# PCBA-2121-01.net
KiCad netlist of a schematic drawn in Altium Designer
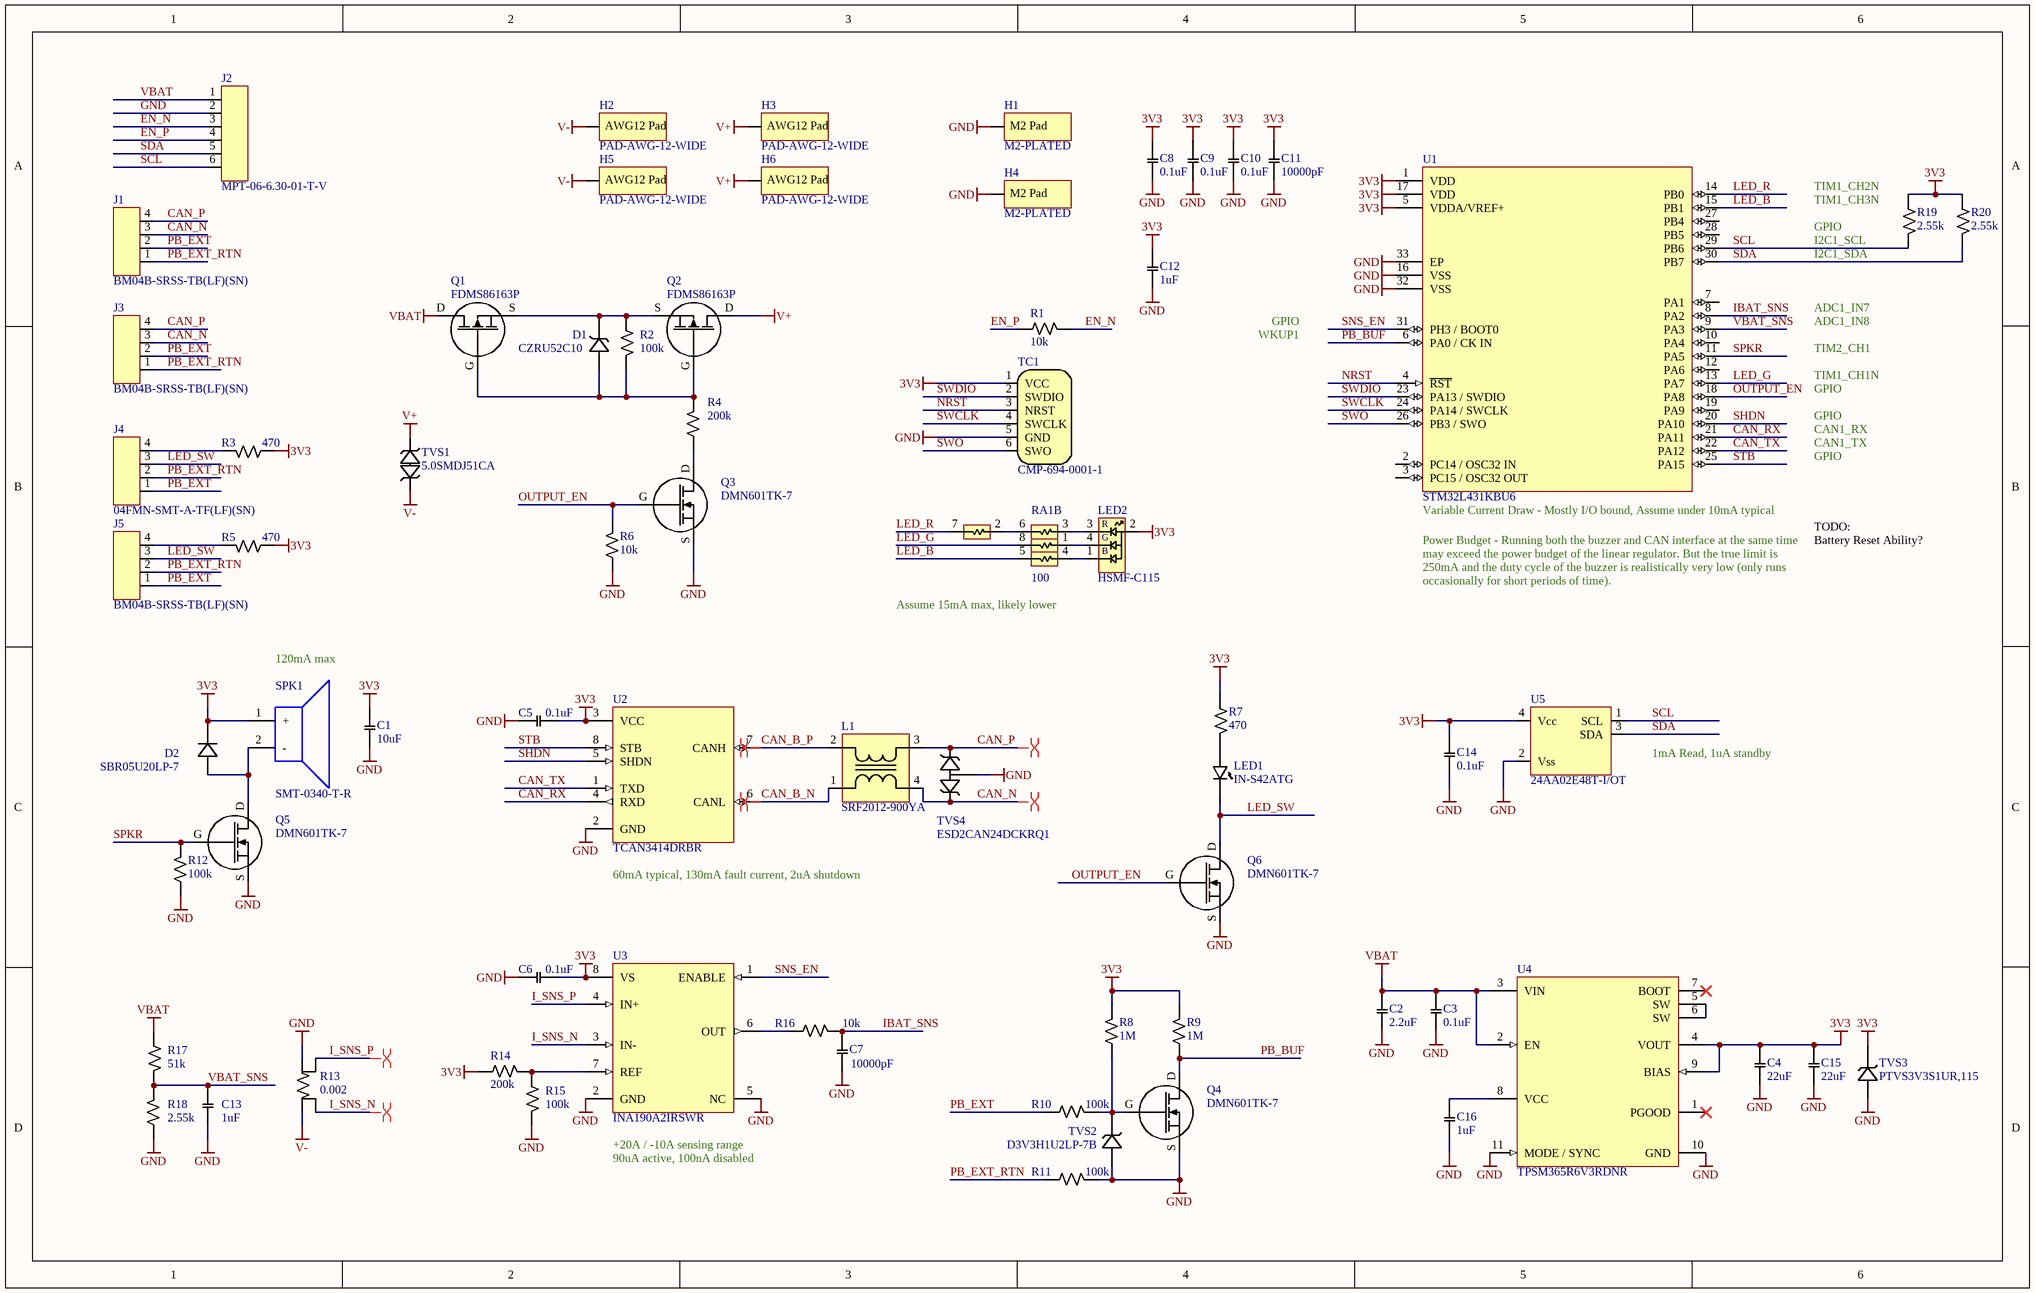
[diagram p0: PCBA-2121-01.SchDoc]

(export (version "E")
  (design (tool "Eeschema 10.0.6"))
  (components
    (comp (ref "C1")
      (value "C-10uf-X5R-16V-10%-0603")
      (footprint "C0603")
      (description "Capacitor Ceramic 10uF 16V X5R 10% SMD 0603")
      (fields (field (name "CAPACITANCE") "10uF") (field (name "TOLERANCE") "10%"))
      (libsource (lib "Hebi Robotics") (part "Capacitor"))
    )
    (comp (ref "C2")
      (value "C-2.2uf-X7R-100V-10%-1206")
      (footprint "C1206")
      (description "Capacitor Ceramic 2.2uF 100V X7R 10% SMD 1206")
      (fields (field (name "CAPACITANCE") "2.2uF") (field (name "TOLERANCE") "±10%"))
      (libsource (lib "Hebi Robotics") (part "Capacitor"))
    )
    (comp (ref "C3")
      (value "C-0.1uf-X7R-100V-20%-0603")
      (footprint "C0603")
      (description "Capacitor Ceramic 0.1uF 100V X7R 20% SMD 0603")
      (fields (field (name "CAPACITANCE") "0.1uF") (field (name "TOLERANCE") "±20%"))
      (libsource (lib "Hebi Robotics") (part "Capacitor"))
    )
    (comp (ref "C4")
      (value "C-22uf-X5R-25V-20%-1206")
      (footprint "C1206")
      (description "Capacitor Ceramic 22uF 25V X5R 20% SMD 1206")
      (fields (field (name "CAPACITANCE") "22uF") (field (name "TOLERANCE") "20%"))
      (libsource (lib "Hebi Robotics") (part "Capacitor"))
    )
    (comp (ref "C5")
      (value "C-0.1uf-X7R-25V-10%-0402")
      (footprint "C0402")
      (description "Capacitor Ceramic 0.1uF 25V X7R 10% SMD 0402")
      (fields (field (name "CAPACITANCE") "0.1uF") (field (name "TOLERANCE") "10%"))
      (libsource (lib "Hebi Robotics") (part "Capacitor"))
    )
    (comp (ref "C6")
      (value "C-0.1uf-X7R-25V-10%-0402")
      (footprint "C0402")
      (description "Capacitor Ceramic 0.1uF 25V X7R 10% SMD 0402")
      (fields (field (name "CAPACITANCE") "0.1uF") (field (name "TOLERANCE") "10%"))
      (libsource (lib "Hebi Robotics") (part "Capacitor"))
    )
    (comp (ref "C7")
      (value "C-10000pf-X7R-50V-10%-0402")
      (footprint "C0402")
      (description "Capacitor Ceramic 10000pF 50V X7R 10% SMD 0402")
      (fields (field (name "TOLERANCE") "10%") (field (name "CAPACITANCE") "10000pF"))
      (libsource (lib "Hebi Robotics") (part "Capacitor"))
    )
    (comp (ref "C8")
      (value "C-0.1uf-X7R-25V-10%-0402")
      (footprint "C0402")
      (description "Capacitor Ceramic 0.1uF 25V X7R 10% SMD 0402")
      (fields (field (name "CAPACITANCE") "0.1uF") (field (name "TOLERANCE") "10%"))
      (libsource (lib "Hebi Robotics") (part "Capacitor"))
    )
    (comp (ref "C9")
      (value "C-0.1uf-X7R-25V-10%-0402")
      (footprint "C0402")
      (description "Capacitor Ceramic 0.1uF 25V X7R 10% SMD 0402")
      (fields (field (name "CAPACITANCE") "0.1uF") (field (name "TOLERANCE") "10%"))
      (libsource (lib "Hebi Robotics") (part "Capacitor"))
    )
    (comp (ref "C10")
      (value "C-0.1uf-X7R-25V-10%-0402")
      (footprint "C0402")
      (description "Capacitor Ceramic 0.1uF 25V X7R 10% SMD 0402")
      (fields (field (name "CAPACITANCE") "0.1uF") (field (name "TOLERANCE") "10%"))
      (libsource (lib "Hebi Robotics") (part "Capacitor"))
    )
    (comp (ref "C11")
      (value "C-10000pf-X7R-50V-10%-0402")
      (footprint "C0402")
      (description "Capacitor Ceramic 10000pF 50V X7R 10% SMD 0402")
      (fields (field (name "TOLERANCE") "10%") (field (name "CAPACITANCE") "10000pF"))
      (libsource (lib "Hebi Robotics") (part "Capacitor"))
    )
    (comp (ref "C12")
      (value "C-1uf-X5R-25V-10%-0402")
      (footprint "C0402")
      (description "Capacitor Ceramic 1uF 25V X5R 10% SMD 0402")
      (fields (field (name "CAPACITANCE") "1uF") (field (name "TOLERANCE") "±10%"))
      (libsource (lib "Hebi Robotics") (part "Capacitor"))
    )
    (comp (ref "C13")
      (value "C-1uf-X5R-25V-10%-0402")
      (footprint "C0402")
      (description "Capacitor Ceramic 1uF 25V X5R 10% SMD 0402")
      (fields (field (name "CAPACITANCE") "1uF") (field (name "TOLERANCE") "±10%"))
      (libsource (lib "Hebi Robotics") (part "Capacitor"))
    )
    (comp (ref "C14")
      (value "C-0.1uf-X7R-25V-10%-0402")
      (footprint "C0402")
      (description "Capacitor Ceramic 0.1uF 25V X7R 10% SMD 0402")
      (fields (field (name "CAPACITANCE") "0.1uF") (field (name "TOLERANCE") "10%"))
      (libsource (lib "Hebi Robotics") (part "Capacitor"))
    )
    (comp (ref "C15")
      (value "C-22uf-X5R-25V-20%-1206")
      (footprint "C1206")
      (description "Capacitor Ceramic 22uF 25V X5R 20% SMD 1206")
      (fields (field (name "CAPACITANCE") "22uF") (field (name "TOLERANCE") "20%"))
      (libsource (lib "Hebi Robotics") (part "Capacitor"))
    )
    (comp (ref "C16")
      (value "C-1uf-X5R-25V-10%-0402")
      (footprint "C0402")
      (description "Capacitor Ceramic 1uF 25V X5R 10% SMD 0402")
      (fields (field (name "CAPACITANCE") "1uF") (field (name "TOLERANCE") "±10%"))
      (libsource (lib "Hebi Robotics") (part "Capacitor"))
    )
    (comp (ref "D1")
      (value "CZRU52C10")
      (footprint "CZRU52C10")
      (description "DIODE ZENER 10V 150MW 0603")
      (libsource (lib "Hebi Robotics") (part "ZENER"))
    )
    (comp (ref "D2")
      (value "SBR05U20LP-7")
      (footprint "DFN1006-2_DIODES")
      (description "DIODE SBR 20V 500MA 2DFN")
      (libsource (lib "Hebi Robotics") (part "DIODE"))
    )
    (comp (ref "H1")
      (value "M2-PLATED")
      (footprint "M2-PLATED-NORMAL")
      (description "M2 Size Screw Hole, Normal Fit, Plated")
      (libsource (lib "Hebi Robotics") (part "MOUNTING_HOLE"))
    )
    (comp (ref "H2")
      (value "PAD-AWG-12-WIDE")
      (footprint "AWG-12-With-Wire")
      (description "AWG 12 Hole with Wider Pad")
      (libsource (lib "Hebi Robotics") (part "WIRE_PAD"))
    )
    (comp (ref "H3")
      (value "PAD-AWG-12-WIDE")
      (footprint "AWG-12-With-Wire")
      (description "AWG 12 Hole with Wider Pad")
      (libsource (lib "Hebi Robotics") (part "WIRE_PAD"))
    )
    (comp (ref "H4")
      (value "M2-PLATED")
      (footprint "M2-PLATED-NORMAL")
      (description "M2 Size Screw Hole, Normal Fit, Plated")
      (libsource (lib "Hebi Robotics") (part "MOUNTING_HOLE"))
    )
    (comp (ref "H5")
      (value "PAD-AWG-12-WIDE")
      (footprint "AWG-12-With-Wire")
      (description "AWG 12 Hole with Wider Pad")
      (libsource (lib "Hebi Robotics") (part "WIRE_PAD"))
    )
    (comp (ref "H6")
      (value "PAD-AWG-12-WIDE")
      (footprint "AWG-12-With-Wire")
      (description "AWG 12 Hole with Wider Pad")
      (libsource (lib "Hebi Robotics") (part "WIRE_PAD"))
    )
    (comp (ref "J1")
      (value "BM04B-SRSS-TB(LF)(SN)")
      (footprint "BM04B-SRSS-TB")
      (description "CONN HEADER SH 4POS TOP 1MM TIN")
      (fields (field (name "MANUFACTURER") "JST Sales America Inc"))
      (libsource (lib "Hebi Robotics") (part "CONN_1_ROW_004_POS"))
    )
    (comp (ref "J2")
      (value "MPT-06-6.30-01-T-V")
      (footprint "MPT-06-6.30-01-T-V-Footprint-1")
      (description "5.00 MM POWERSTRIP/30 A DUAL BL")
      (libsource (lib "Hebi Robotics") (part "CONN_1_ROW_006_POS"))
    )
    (comp (ref "J3")
      (value "BM04B-SRSS-TB(LF)(SN)")
      (footprint "BM04B-SRSS-TB")
      (description "CONN HEADER SH 4POS TOP 1MM TIN")
      (fields (field (name "MANUFACTURER") "JST Sales America Inc"))
      (libsource (lib "Hebi Robotics") (part "CONN_1_ROW_004_POS"))
    )
    (comp (ref "J4")
      (value "04FMN-SMT-A-TF(LF)(SN)")
      (footprint "04FMN-SMT-A-TF(LF)(SN)-Footprint-1")
      (description "Ffc / Fpc Board Connector, Fmn Series, Surface Mount, Receptacle, 4, 1 Mm Rohs Compliant: Yes")
      (libsource (lib "Hebi Robotics") (part "CONN_1_ROW_004_POS"))
    )
    (comp (ref "J5")
      (value "BM04B-SRSS-TB(LF)(SN)")
      (footprint "BM04B-SRSS-TB")
      (description "CONN HEADER SH 4POS TOP 1MM TIN")
      (fields (field (name "MANUFACTURER") "JST Sales America Inc"))
      (libsource (lib "Hebi Robotics") (part "CONN_1_ROW_004_POS"))
    )
    (comp (ref "L1")
      (value "SRF2012-900YA")
      (footprint "FP-SRF2012A-MFG")
      (description "CMC 400MA 2LN 90 OHM SMD")
      (libsource (lib "Hebi Robotics") (part "CM_CHOKE_4PIN"))
    )
    (comp (ref "LED1")
      (value "IN-S42ATG")
      (footprint "IN-S42AT")
      (description "LED GREEN CLEAR 0402 SMD")
      (libsource (lib "Hebi Robotics") (part "LED"))
    )
    (comp (ref "LED2")
      (value "HSMF-C115")
      (footprint "HSMF-C115")
      (description "LED RGB DIFFUSED CHIP SMD R/A")
      (libsource (lib "Hebi Robotics") (part "HSMF-C115"))
    )
    (comp (ref "Q1")
      (value "FDMS86163P")
      (footprint "FDMS86300DC")
      (description "MOSFET P-CH 100V 7.9A POWER56")
      (libsource (lib "Hebi Robotics") (part "P_MOSFET"))
    )
    (comp (ref "Q2")
      (value "FDMS86163P")
      (footprint "FDMS86300DC")
      (description "MOSFET P-CH 100V 7.9A POWER56")
      (libsource (lib "Hebi Robotics") (part "P_MOSFET"))
    )
    (comp (ref "Q3")
      (value "DMN601TK-7")
      (footprint "SOT50P160X80-3L")
      (description "MOSFET N-CH 60V 300MA SOT-523")
      (libsource (lib "Hebi Robotics") (part "N_MOSFET"))
    )
    (comp (ref "Q4")
      (value "DMN601TK-7")
      (footprint "SOT50P160X80-3L")
      (description "MOSFET N-CH 60V 300MA SOT-523")
      (libsource (lib "Hebi Robotics") (part "N_MOSFET"))
    )
    (comp (ref "Q5")
      (value "DMN601TK-7")
      (footprint "SOT50P160X80-3L")
      (description "MOSFET N-CH 60V 300MA SOT-523")
      (libsource (lib "Hebi Robotics") (part "N_MOSFET"))
    )
    (comp (ref "Q6")
      (value "DMN601TK-7")
      (footprint "SOT50P160X80-3L")
      (description "MOSFET N-CH 60V 300MA SOT-523")
      (libsource (lib "Hebi Robotics") (part "N_MOSFET"))
    )
    (comp (ref "R1")
      (value "R-10k-1%-0.063w-0402")
      (footprint "R0402")
      (description "Resistor 0402 10k Ohm 1% 1-16 Watt")
      (fields
        (field (name "POWER") "0.063W, 1/16W")
        (field (name "RESISTANCE") "10k")
        (field (name "TOLERANCE") "1%")
      )
      (libsource (lib "Hebi Robotics") (part "Resistor"))
    )
    (comp (ref "R2")
      (value "R-100k-1%-0.063w-0402")
      (footprint "R0402")
      (description "Resistor 0402 100k Ohm 1% 1-16 Watt")
      (fields
        (field (name "POWER") "0.063W, 1/16W")
        (field (name "RESISTANCE") "100k")
        (field (name "TOLERANCE") "1%")
      )
      (libsource (lib "Hebi Robotics") (part "Resistor"))
    )
    (comp (ref "R3")
      (value "R-470-1%-0.063w-0402")
      (footprint "R0402")
      (description "Resistor 0402 470 Ohm 1% 1-16 Watt")
      (fields
        (field (name "POWER") "0.063W, 1/16W")
        (field (name "TOLERANCE") "1%")
        (field (name "RESISTANCE") "470")
      )
      (libsource (lib "Hebi Robotics") (part "Resistor"))
    )
    (comp (ref "R4")
      (value "R-200k-1%-0.063w-0402")
      (footprint "R0402")
      (description "Resistor 0402 200k Ohm 1% 1-16 Watt")
      (fields
        (field (name "POWER") "0.063W, 1/16W")
        (field (name "RESISTANCE") "200k")
        (field (name "TOLERANCE") "1%")
      )
      (libsource (lib "Hebi Robotics") (part "Resistor"))
    )
    (comp (ref "R5")
      (value "R-470-1%-0.063w-0402")
      (footprint "R0402")
      (description "Resistor 0402 470 Ohm 1% 1-16 Watt")
      (fields
        (field (name "POWER") "0.063W, 1/16W")
        (field (name "TOLERANCE") "1%")
        (field (name "RESISTANCE") "470")
      )
      (libsource (lib "Hebi Robotics") (part "Resistor"))
    )
    (comp (ref "R6")
      (value "R-10k-1%-0.063w-0402")
      (footprint "R0402")
      (description "Resistor 0402 10k Ohm 1% 1-16 Watt")
      (fields
        (field (name "POWER") "0.063W, 1/16W")
        (field (name "RESISTANCE") "10k")
        (field (name "TOLERANCE") "1%")
      )
      (libsource (lib "Hebi Robotics") (part "Resistor"))
    )
    (comp (ref "R7")
      (value "R-470-1%-0.063w-0402")
      (footprint "R0402")
      (description "Resistor 0402 470 Ohm 1% 1-16 Watt")
      (fields
        (field (name "POWER") "0.063W, 1/16W")
        (field (name "TOLERANCE") "1%")
        (field (name "RESISTANCE") "470")
      )
      (libsource (lib "Hebi Robotics") (part "Resistor"))
    )
    (comp (ref "R8")
      (value "R-1M-1%-0.063w-0402")
      (footprint "R0402")
      (description "Resistor 0402 1M Ohm 1% 1-16 Watt")
      (fields
        (field (name "RESISTANCE") "1M")
        (field (name "POWER") "0.063W, 1/16W")
        (field (name "TOLERANCE") "1%")
      )
      (libsource (lib "Hebi Robotics") (part "Resistor"))
    )
    (comp (ref "R9")
      (value "R-1M-1%-0.063w-0402")
      (footprint "R0402")
      (description "Resistor 0402 1M Ohm 1% 1-16 Watt")
      (fields
        (field (name "RESISTANCE") "1M")
        (field (name "POWER") "0.063W, 1/16W")
        (field (name "TOLERANCE") "1%")
      )
      (libsource (lib "Hebi Robotics") (part "Resistor"))
    )
    (comp (ref "R10")
      (value "R-100k-1%-0.063w-0402")
      (footprint "R0402")
      (description "Resistor 0402 100k Ohm 1% 1-16 Watt")
      (fields
        (field (name "POWER") "0.063W, 1/16W")
        (field (name "RESISTANCE") "100k")
        (field (name "TOLERANCE") "1%")
      )
      (libsource (lib "Hebi Robotics") (part "Resistor"))
    )
    (comp (ref "R11")
      (value "R-100k-1%-0.063w-0402")
      (footprint "R0402")
      (description "Resistor 0402 100k Ohm 1% 1-16 Watt")
      (fields
        (field (name "POWER") "0.063W, 1/16W")
        (field (name "RESISTANCE") "100k")
        (field (name "TOLERANCE") "1%")
      )
      (libsource (lib "Hebi Robotics") (part "Resistor"))
    )
    (comp (ref "R12")
      (value "R-100k-1%-0.063w-0402")
      (footprint "R0402")
      (description "Resistor 0402 100k Ohm 1% 1-16 Watt")
      (fields
        (field (name "POWER") "0.063W, 1/16W")
        (field (name "TOLERANCE") "1%")
        (field (name "RESISTANCE") "100k")
      )
      (libsource (lib "Hebi Robotics") (part "Resistor"))
    )
    (comp (ref "R13")
      (value "WSKW06122L000FEA")
      (footprint "WSKW0612")
      (description "RES 0.002 OHM 1W 0612 KELVIN")
      (fields (field (name "RESISTANCE") "0.002"))
      (libsource (lib "Hebi Robotics") (part "R_4"))
    )
    (comp (ref "R14")
      (value "R-200k-1%-0.063w-0402")
      (footprint "R0402")
      (description "Resistor 0402 200k Ohm 1% 1-16 Watt")
      (fields
        (field (name "POWER") "0.063W, 1/16W")
        (field (name "RESISTANCE") "200k")
        (field (name "TOLERANCE") "1%")
      )
      (libsource (lib "Hebi Robotics") (part "Resistor"))
    )
    (comp (ref "R15")
      (value "R-100k-1%-0.063w-0402")
      (footprint "R0402")
      (description "Resistor 0402 100k Ohm 1% 1-16 Watt")
      (fields
        (field (name "POWER") "0.063W, 1/16W")
        (field (name "RESISTANCE") "100k")
        (field (name "TOLERANCE") "1%")
      )
      (libsource (lib "Hebi Robotics") (part "Resistor"))
    )
    (comp (ref "R16")
      (value "R-10k-1%-0.063w-0402")
      (footprint "R0402")
      (description "Resistor 0402 10k Ohm 1% 1-16 Watt")
      (fields
        (field (name "TOLERANCE") "1%")
        (field (name "RESISTANCE") "10k")
        (field (name "POWER") "0.063W, 1/16W")
      )
      (libsource (lib "Hebi Robotics") (part "Resistor"))
    )
    (comp (ref "R17")
      (value "R-51k-1%-0.063w-0402")
      (footprint "R0402")
      (description "Resistor 0402 51k Ohm 1% 1-16 Watt")
      (fields (field (name "POWER") "0.063W, 1/16W") (field (name "RESISTANCE") "51k"))
      (libsource (lib "Hebi Robotics") (part "Resistor"))
    )
    (comp (ref "R18")
      (value "R-2.55k-1%-0.063w-0402")
      (footprint "R0402")
      (description "Resistor 0402 2.55k Ohm 1% 1-16 Watt")
      (fields (field (name "POWER") "0.063W, 1/16W") (field (name "RESISTANCE") "2.55k"))
      (libsource (lib "Hebi Robotics") (part "Resistor"))
    )
    (comp (ref "R19")
      (value "R-2.55k-1%-0.063w-0402")
      (footprint "R0402")
      (description "Resistor 0402 2.55k Ohm 1% 1-16 Watt")
      (fields (field (name "RESISTANCE") "2.55k") (field (name "POWER") "0.063W, 1/16W"))
      (libsource (lib "Hebi Robotics") (part "Resistor"))
    )
    (comp (ref "R20")
      (value "R-2.55k-1%-0.063w-0402")
      (footprint "R0402")
      (description "Resistor 0402 2.55k Ohm 1% 1-16 Watt")
      (fields (field (name "RESISTANCE") "2.55k") (field (name "POWER") "0.063W, 1/16W"))
      (libsource (lib "Hebi Robotics") (part "Resistor"))
    )
    (comp (ref "RA1")
      (value "RA-4-C-100-5%-0.063w-0804")
      (footprint "741C083")
      (description "100 ohm Resistor Array 4 Element Concave 5%  1-16Watt 0804")
      (fields (field (name "POWER") "0.063W") (field (name "RESISTANCE") "100"))
      (libsource (lib "Hebi Robotics") (part "RA4"))
    )
    (comp (ref "SPK1")
      (value "SMT-0340-T-R")
      (footprint "SMT-0340-T-R")
      (description "BUZZER MAGNETIC 3V 3.2X3.2MM SMD")
      (fields (field (name "VOLTAGE") "3V"))
      (libsource (lib "Hebi Robotics") (part "Speaker"))
    )
    (comp (ref "TC1")
      (value "CMP-694-0001-1")
      (footprint "TC2030-MCP-NL_SMALL")
      (description "TC2030-MCP-NL")
      (fields (field (name "MANUFACTURER PART NUMBER") "TC2030-MCP-NL_SMALL"))
      (libsource (lib "Hebi Robotics") (part "TC2030-MCP-NL"))
    )
    (comp (ref "TVS1")
      (value "5.0SMDJ51CA")
      (footprint "DIOM6959X26L")
      (description "TVS DIODE 51VWM 82.4VC DO214AB")
      (libsource (lib "Hebi Robotics") (part "TVS_BI"))
    )
    (comp (ref "TVS2")
      (value "D3V3H1U2LP-7B")
      (footprint "DFN70P101X53-2N")
      (description "TVS DIODE 3.3V 10V DFN1006-2")
      (libsource (lib "Hebi Robotics") (part "TVS"))
    )
    (comp (ref "TVS3")
      (value "PTVS3V3S1UR,115")
      (footprint "SOD-123W_NXP")
      (description "TVS DIODE 3.3VWM 8VC SOD123W")
      (libsource (lib "Hebi Robotics") (part "TVS"))
    )
    (comp (ref "TVS4")
      (value "ESD2CAN24DCKRQ1")
      (footprint "SOT65P210X90-3L")
      (description "TVS DIODE 24VWM 37VC CAN SC703")
      (libsource (lib "Hebi Robotics") (part "ESD2CAN24DCKRQ1-Symbol-1"))
    )
    (comp (ref "U1")
      (value "STM32L431KBU6")
      (footprint "QFN50P500X500X60_HS-33L")
      (description "IC MCU 32BIT 128KB FLSH 32UFQFPN")
      (libsource (lib "Hebi Robotics") (part "STM32L412K8U6"))
    )
    (comp (ref "U2")
      (value "TCAN3414DRBR")
      (footprint "SON65P300X100_HS-9L")
      (description "IC TRANSCEIVER HALF 1/1 8SON")
      (libsource (lib "Hebi Robotics") (part "TCAN3414DRBR-Symbol-1"))
    )
    (comp (ref "U3")
      (value "INA190A2IRSWR")
      (footprint "QFN40P140X180X55-10L")
      (description "IC CURR SENSE 1 CIRCUIT 10UQFN")
      (libsource (lib "Hebi Robotics") (part "INA190A2IRSWR-Symbol-1"))
    )
    (comp (ref "U4")
      (value "TPSM365R6V3RDNR")
      (footprint "TPSM365R6V3RDNR-Footprint-1")
      (description "3-V TO 65-V INPUT, 3V3 OUT, 300mA")
      (libsource (lib "Hebi Robotics") (part "TPSM365R6V3RDNR-Symbol-1"))
    )
    (comp (ref "U5")
      (value "24AA02E48T-I/OT")
      (footprint "SOT95P280X100-5N")
      (description "IC EEPROM 2KBIT 400KHZ SOT23-5")
      (fields (field (name "MANUFACTURER") "Microchip Technology"))
      (libsource (lib "Hebi Robotics") (part "24AA02E48T-I/OT"))
    )
  )
  (nets
    (net (code "1") (name "/CAN_B_N") (class "Default")
      (node (ref "L1") (pin "1") (pinfunction "1_1") (pintype "passive"))
      (node (ref "U2") (pin "6") (pinfunction "CANL_6") (pintype "bidirectional"))
    )
    (net (code "2") (name "/CAN_B_P") (class "Default")
      (node (ref "L1") (pin "2") (pinfunction "2_2") (pintype "passive"))
      (node (ref "U2") (pin "7") (pinfunction "CANH_7") (pintype "bidirectional"))
    )
    (net (code "3") (name "/CAN_N") (class "Default")
      (node (ref "J1") (pin "3") (pinfunction "3_3") (pintype "passive"))
      (node (ref "J3") (pin "3") (pinfunction "3_3") (pintype "passive"))
      (node (ref "L1") (pin "4") (pinfunction "4_4") (pintype "passive"))
      (node (ref "TVS4") (pin "1") (pinfunction "1_1") (pintype "passive"))
    )
    (net (code "4") (name "/CAN_P") (class "Default")
      (node (ref "J1") (pin "4") (pinfunction "4_4") (pintype "passive"))
      (node (ref "J3") (pin "4") (pinfunction "4_4") (pintype "passive"))
      (node (ref "L1") (pin "3") (pinfunction "3_3") (pintype "passive"))
      (node (ref "TVS4") (pin "2") (pinfunction "2_2") (pintype "passive"))
    )
    (net (code "5") (name "/CAN_RX") (class "Default")
      (node (ref "U1") (pin "21") (pinfunction "PA11_21") (pintype "bidirectional"))
      (node (ref "U2") (pin "4") (pinfunction "RXD_4") (pintype "output"))
    )
    (net (code "6") (name "/CAN_TX") (class "Default")
      (node (ref "U1") (pin "22") (pinfunction "PA12_22") (pintype "bidirectional"))
      (node (ref "U2") (pin "1") (pinfunction "TXD_1") (pintype "input"))
    )
    (net (code "7") (name "/EN_N") (class "Default")
      (node (ref "J2") (pin "3") (pinfunction "3_3") (pintype "passive"))
      (node (ref "R1") (pin "2") (pinfunction "2_2") (pintype "passive"))
    )
    (net (code "8") (name "/EN_P") (class "Default")
      (node (ref "J2") (pin "4") (pinfunction "4_4") (pintype "passive"))
      (node (ref "R1") (pin "1") (pinfunction "1_1") (pintype "passive"))
    )
    (net (code "9") (name "/IBAT_SNS") (class "Default")
      (node (ref "C7") (pin "2") (pinfunction "2_2") (pintype "passive"))
      (node (ref "R16") (pin "2") (pinfunction "2_2") (pintype "passive"))
      (node (ref "U1") (pin "8") (pinfunction "PA2_8") (pintype "bidirectional"))
    )
    (net (code "10") (name "/I_SNS_N") (class "Default")
      (node (ref "R13") (pin "4") (pinfunction "4_4") (pintype "passive"))
      (node (ref "U3") (pin "3") (pinfunction "IN-_3") (pintype "input"))
    )
    (net (code "11") (name "/I_SNS_P") (class "Default")
      (node (ref "R13") (pin "3") (pinfunction "3_3") (pintype "passive"))
      (node (ref "U3") (pin "4") (pinfunction "IN+_4") (pintype "input"))
    )
    (net (code "12") (name "/LED_B") (class "Default")
      (node (ref "RA1") (pin "5") (pinfunction "5_5") (pintype "passive"))
      (node (ref "U1") (pin "15") (pinfunction "PB1_15") (pintype "bidirectional"))
    )
    (net (code "13") (name "/LED_G") (class "Default")
      (node (ref "RA1") (pin "8") (pinfunction "8_8") (pintype "passive"))
      (node (ref "U1") (pin "13") (pinfunction "PA7_13") (pintype "bidirectional"))
    )
    (net (code "14") (name "/LED_R") (class "Default")
      (node (ref "RA1") (pin "7") (pinfunction "7_7") (pintype "passive"))
      (node (ref "U1") (pin "14") (pinfunction "PB0_14") (pintype "bidirectional"))
    )
    (net (code "15") (name "/LED_SW") (class "Default")
      (node (ref "J4") (pin "3") (pinfunction "3_3") (pintype "passive"))
      (node (ref "J5") (pin "3") (pinfunction "3_3") (pintype "passive"))
      (node (ref "LED1") (pin "C") (pinfunction "C_C") (pintype "passive"))
      (node (ref "Q6") (pin "D") (pinfunction "D_D") (pintype "passive"))
    )
    (net (code "16") (name "/NRST") (class "Default")
      (node (ref "TC1") (pin "3") (pinfunction "NRST_3") (pintype "passive"))
      (node (ref "U1") (pin "4") (pinfunction "~{RST}_4") (pintype "input"))
    )
    (net (code "17") (name "/OUTPUT_EN") (class "Default")
      (node (ref "Q3") (pin "G") (pinfunction "G_G") (pintype "passive"))
      (node (ref "Q6") (pin "G") (pinfunction "G_G") (pintype "passive"))
      (node (ref "R6") (pin "2") (pinfunction "2_2") (pintype "passive"))
      (node (ref "U1") (pin "18") (pinfunction "PA8_18") (pintype "bidirectional"))
    )
    (net (code "18") (name "/PB_BUF") (class "Default")
      (node (ref "Q4") (pin "D") (pinfunction "D_D") (pintype "passive"))
      (node (ref "R9") (pin "1") (pinfunction "1_1") (pintype "passive"))
      (node (ref "U1") (pin "6") (pinfunction "PA0_/_CK_IN_6") (pintype "bidirectional"))
    )
    (net (code "19") (name "/PB_EXT") (class "Default")
      (node (ref "J1") (pin "2") (pinfunction "2_2") (pintype "passive"))
      (node (ref "J3") (pin "2") (pinfunction "2_2") (pintype "passive"))
      (node (ref "J4") (pin "1") (pinfunction "1_1") (pintype "passive"))
      (node (ref "J5") (pin "1") (pinfunction "1_1") (pintype "passive"))
      (node (ref "R10") (pin "1") (pinfunction "1_1") (pintype "passive"))
    )
    (net (code "20") (name "/PB_EXT_RTN") (class "Default")
      (node (ref "J1") (pin "1") (pinfunction "1_1") (pintype "passive"))
      (node (ref "J3") (pin "1") (pinfunction "1_1") (pintype "passive"))
      (node (ref "J4") (pin "2") (pinfunction "2_2") (pintype "passive"))
      (node (ref "J5") (pin "2") (pinfunction "2_2") (pintype "passive"))
      (node (ref "R11") (pin "1") (pinfunction "1_1") (pintype "passive"))
    )
    (net (code "21") (name "/SCL") (class "Default")
      (node (ref "J2") (pin "6") (pinfunction "6_6") (pintype "passive"))
      (node (ref "R19") (pin "2") (pinfunction "2_2") (pintype "passive"))
      (node (ref "U1") (pin "29") (pinfunction "PB6_29") (pintype "bidirectional"))
      (node (ref "U5") (pin "1") (pinfunction "SCL_1") (pintype "open_collector"))
    )
    (net (code "22") (name "/SDA") (class "Default")
      (node (ref "J2") (pin "5") (pinfunction "5_5") (pintype "passive"))
      (node (ref "R20") (pin "2") (pinfunction "2_2") (pintype "passive"))
      (node (ref "U1") (pin "30") (pinfunction "PB7_30") (pintype "bidirectional"))
      (node (ref "U5") (pin "3") (pinfunction "SDA_3") (pintype "open_collector"))
    )
    (net (code "23") (name "/SHDN") (class "Default")
      (node (ref "U1") (pin "20") (pinfunction "PA10_20") (pintype "bidirectional"))
      (node (ref "U2") (pin "5") (pinfunction "SHDN_5") (pintype "input"))
    )
    (net (code "24") (name "/SNS_EN") (class "Default")
      (node (ref "U1") (pin "31") (pinfunction "PH3_/_BOOT0_31") (pintype "bidirectional"))
      (node (ref "U3") (pin "1") (pinfunction "ENABLE_1") (pintype "input"))
    )
    (net (code "25") (name "/SPKR") (class "Default")
      (node (ref "Q5") (pin "G") (pinfunction "G_G") (pintype "passive"))
      (node (ref "R12") (pin "2") (pinfunction "2_2") (pintype "passive"))
      (node (ref "U1") (pin "11") (pinfunction "PA5_11") (pintype "bidirectional"))
    )
    (net (code "26") (name "/STB") (class "Default")
      (node (ref "U1") (pin "25") (pinfunction "PA15_25") (pintype "bidirectional"))
      (node (ref "U2") (pin "8") (pinfunction "STB_8") (pintype "input"))
    )
    (net (code "27") (name "/SWCLK") (class "Default")
      (node (ref "TC1") (pin "4") (pinfunction "SWCLK_4") (pintype "passive"))
      (node (ref "U1") (pin "24") (pinfunction "PA14_/_SWCLK_24") (pintype "bidirectional"))
    )
    (net (code "28") (name "/SWDIO") (class "Default")
      (node (ref "TC1") (pin "2") (pinfunction "SWDIO_2") (pintype "passive"))
      (node (ref "U1") (pin "23") (pinfunction "PA13_/_SWDIO_23") (pintype "bidirectional"))
    )
    (net (code "29") (name "/SWO") (class "Default")
      (node (ref "TC1") (pin "6") (pinfunction "SWO_6") (pintype "passive"))
      (node (ref "U1") (pin "26") (pinfunction "PB3_/_SWO_26") (pintype "bidirectional"))
    )
    (net (code "30") (name "/VBAT_SNS") (class "Default")
      (node (ref "C13") (pin "1") (pinfunction "1_1") (pintype "passive"))
      (node (ref "R17") (pin "2") (pinfunction "2_2") (pintype "passive"))
      (node (ref "R18") (pin "2") (pinfunction "2_2") (pintype "passive"))
      (node (ref "U1") (pin "9") (pinfunction "PA3_9") (pintype "bidirectional"))
    )
    (net (code "31") (name "3V3") (class "Default")
      (node (ref "C1") (pin "1") (pinfunction "1_1") (pintype "passive"))
      (node (ref "C10") (pin "2") (pinfunction "2_2") (pintype "passive"))
      (node (ref "C11") (pin "2") (pinfunction "2_2") (pintype "passive"))
      (node (ref "C12") (pin "1") (pinfunction "1_1") (pintype "passive"))
      (node (ref "C14") (pin "2") (pinfunction "2_2") (pintype "passive"))
      (node (ref "C15") (pin "2") (pinfunction "2_2") (pintype "passive"))
      (node (ref "C4") (pin "2") (pinfunction "2_2") (pintype "passive"))
      (node (ref "C5") (pin "2") (pinfunction "2_2") (pintype "passive"))
      (node (ref "C6") (pin "2") (pinfunction "2_2") (pintype "passive"))
      (node (ref "C8") (pin "2") (pinfunction "2_2") (pintype "passive"))
      (node (ref "C9") (pin "2") (pinfunction "2_2") (pintype "passive"))
      (node (ref "D2") (pin "C") (pinfunction "C_C") (pintype "passive"))
      (node (ref "LED2") (pin "2") (pinfunction "A_2") (pintype "passive"))
      (node (ref "R14") (pin "1") (pinfunction "1_1") (pintype "passive"))
      (node (ref "R19") (pin "1") (pinfunction "1_1") (pintype "passive"))
      (node (ref "R20") (pin "1") (pinfunction "1_1") (pintype "passive"))
      (node (ref "R3") (pin "1") (pinfunction "1_1") (pintype "passive"))
      (node (ref "R5") (pin "1") (pinfunction "1_1") (pintype "passive"))
      (node (ref "R7") (pin "1") (pinfunction "1_1") (pintype "passive"))
      (node (ref "R8") (pin "2") (pinfunction "2_2") (pintype "passive"))
      (node (ref "R9") (pin "2") (pinfunction "2_2") (pintype "passive"))
      (node (ref "SPK1") (pin "1") (pinfunction "+_1") (pintype "passive"))
      (node (ref "TC1") (pin "1") (pinfunction "VCC_1") (pintype "passive"))
      (node (ref "TVS3") (pin "C") (pinfunction "C_C") (pintype "passive"))
      (node (ref "U1") (pin "1") (pinfunction "VDD_1") (pintype "power_in"))
      (node (ref "U1") (pin "17") (pinfunction "VDD_17") (pintype "power_in"))
      (node (ref "U1") (pin "5") (pinfunction "VDDA/VREF+_5") (pintype "power_in"))
      (node (ref "U2") (pin "3") (pinfunction "VCC_3") (pintype "power_in"))
      (node (ref "U3") (pin "8") (pinfunction "VS_8") (pintype "power_in"))
      (node (ref "U4") (pin "4") (pinfunction "VOUT_4") (pintype "power_in"))
      (node (ref "U4") (pin "9") (pinfunction "BIAS_9") (pintype "input"))
      (node (ref "U5") (pin "4") (pinfunction "Vcc_4") (pintype "power_in"))
    )
    (net (code "32") (name "GND") (class "Default")
      (node (ref "C1") (pin "2") (pinfunction "2_2") (pintype "passive"))
      (node (ref "C10") (pin "1") (pinfunction "1_1") (pintype "passive"))
      (node (ref "C11") (pin "1") (pinfunction "1_1") (pintype "passive"))
      (node (ref "C12") (pin "2") (pinfunction "2_2") (pintype "passive"))
      (node (ref "C13") (pin "2") (pinfunction "2_2") (pintype "passive"))
      (node (ref "C14") (pin "1") (pinfunction "1_1") (pintype "passive"))
      (node (ref "C15") (pin "1") (pinfunction "1_1") (pintype "passive"))
      (node (ref "C16") (pin "1") (pinfunction "1_1") (pintype "passive"))
      (node (ref "C2") (pin "1") (pinfunction "1_1") (pintype "passive"))
      (node (ref "C3") (pin "1") (pinfunction "1_1") (pintype "passive"))
      (node (ref "C4") (pin "1") (pinfunction "1_1") (pintype "passive"))
      (node (ref "C5") (pin "1") (pinfunction "1_1") (pintype "passive"))
      (node (ref "C6") (pin "1") (pinfunction "1_1") (pintype "passive"))
      (node (ref "C7") (pin "1") (pinfunction "1_1") (pintype "passive"))
      (node (ref "C8") (pin "1") (pinfunction "1_1") (pintype "passive"))
      (node (ref "C9") (pin "1") (pinfunction "1_1") (pintype "passive"))
      (node (ref "H1") (pin "HOLE") (pinfunction "HOLE_HOLE") (pintype "passive"))
      (node (ref "H4") (pin "HOLE") (pinfunction "HOLE_HOLE") (pintype "passive"))
      (node (ref "J2") (pin "2") (pinfunction "2_2") (pintype "passive"))
      (node (ref "Q3") (pin "S") (pinfunction "S_S") (pintype "passive"))
      (node (ref "Q4") (pin "S") (pinfunction "S_S") (pintype "passive"))
      (node (ref "Q5") (pin "S") (pinfunction "S_S") (pintype "passive"))
      (node (ref "Q6") (pin "S") (pinfunction "S_S") (pintype "passive"))
      (node (ref "R11") (pin "2") (pinfunction "2_2") (pintype "passive"))
      (node (ref "R12") (pin "1") (pinfunction "1_1") (pintype "passive"))
      (node (ref "R13") (pin "1") (pinfunction "1_1") (pintype "passive"))
      (node (ref "R15") (pin "2") (pinfunction "2_2") (pintype "passive"))
      (node (ref "R18") (pin "1") (pinfunction "1_1") (pintype "passive"))
      (node (ref "R6") (pin "1") (pinfunction "1_1") (pintype "passive"))
      (node (ref "TC1") (pin "5") (pinfunction "GND_5") (pintype "passive"))
      (node (ref "TVS2") (pin "A") (pinfunction "A_A") (pintype "passive"))
      (node (ref "TVS3") (pin "A") (pinfunction "A_A") (pintype "passive"))
      (node (ref "TVS4") (pin "3") (pinfunction "3_3") (pintype "passive"))
      (node (ref "U1") (pin "16") (pinfunction "VSS_16") (pintype "power_in"))
      (node (ref "U1") (pin "32") (pinfunction "VSS_32") (pintype "power_in"))
      (node (ref "U1") (pin "33") (pinfunction "EP_33") (pintype "power_in"))
      (node (ref "U2") (pin "2") (pinfunction "GND_2") (pintype "passive"))
      (node (ref "U3") (pin "2") (pinfunction "GND_2") (pintype "passive"))
      (node (ref "U3") (pin "5") (pinfunction "NC_5") (pintype "passive"))
      (node (ref "U4") (pin "10") (pinfunction "GND_10") (pintype "passive"))
      (node (ref "U4") (pin "11") (pinfunction "MODE_/_SYNC_11") (pintype "input"))
      (node (ref "U5") (pin "2") (pinfunction "Vss_2") (pintype "power_in"))
    )
    (net (code "33") (name "Net-(D1-PadA)") (class "Default")
      (node (ref "D1") (pin "A") (pinfunction "A_A") (pintype "passive"))
      (node (ref "Q1") (pin "G") (pinfunction "G_G") (pintype "passive"))
      (node (ref "Q2") (pin "G") (pinfunction "G_G") (pintype "passive"))
      (node (ref "R2") (pin "2") (pinfunction "2_2") (pintype "passive"))
      (node (ref "R4") (pin "2") (pinfunction "2_2") (pintype "passive"))
    )
    (net (code "34") (name "Net-(D1-PadC)") (class "Default")
      (node (ref "D1") (pin "C") (pinfunction "C_C") (pintype "passive"))
      (node (ref "Q1") (pin "S") (pinfunction "S_S") (pintype "passive"))
      (node (ref "Q2") (pin "S") (pinfunction "S_S") (pintype "passive"))
      (node (ref "R2") (pin "1") (pinfunction "1_1") (pintype "passive"))
    )
    (net (code "35") (name "Net-(J4-Pad4)") (class "Default")
      (node (ref "J4") (pin "4") (pinfunction "4_4") (pintype "passive"))
      (node (ref "R3") (pin "2") (pinfunction "2_2") (pintype "passive"))
    )
    (net (code "36") (name "Net-(J5-Pad4)") (class "Default")
      (node (ref "J5") (pin "4") (pinfunction "4_4") (pintype "passive"))
      (node (ref "R5") (pin "2") (pinfunction "2_2") (pintype "passive"))
    )
    (net (code "37") (name "Net-(LED1-PadA)") (class "Default")
      (node (ref "LED1") (pin "A") (pinfunction "A_A") (pintype "passive"))
      (node (ref "R7") (pin "2") (pinfunction "2_2") (pintype "passive"))
    )
    (net (code "38") (name "Net-(LED2-CB)") (class "Default")
      (node (ref "LED2") (pin "3") (pinfunction "CB_3") (pintype "passive"))
      (node (ref "RA1") (pin "3") (pinfunction "3_3") (pintype "passive"))
    )
    (net (code "39") (name "Net-(LED2-CG)") (class "Default")
      (node (ref "LED2") (pin "4") (pinfunction "CG_4") (pintype "passive"))
      (node (ref "RA1") (pin "1") (pinfunction "1_1") (pintype "passive"))
    )
    (net (code "40") (name "Net-(LED2-CR)") (class "Default")
      (node (ref "LED2") (pin "1") (pinfunction "CR_1") (pintype "passive"))
      (node (ref "RA1") (pin "4") (pinfunction "4_4") (pintype "passive"))
    )
    (net (code "41") (name "Net-(Q3-PadD)") (class "Default")
      (node (ref "Q3") (pin "D") (pinfunction "D_D") (pintype "passive"))
      (node (ref "R4") (pin "1") (pinfunction "1_1") (pintype "passive"))
    )
    (net (code "42") (name "Net-(Q4-PadG)") (class "Default")
      (node (ref "Q4") (pin "G") (pinfunction "G_G") (pintype "passive"))
      (node (ref "R10") (pin "2") (pinfunction "2_2") (pintype "passive"))
      (node (ref "R8") (pin "1") (pinfunction "1_1") (pintype "passive"))
      (node (ref "TVS2") (pin "C") (pinfunction "C_C") (pintype "passive"))
    )
    (net (code "43") (name "Net-(RA1-Pad2)") (class "Default")
      (node (ref "RA1") (pin "2") (pinfunction "2_2") (pintype "passive"))
      (node (ref "RA1") (pin "6") (pinfunction "6_6") (pintype "passive"))
    )
    (net (code "44") (name "Net-(SPK1--)") (class "Default")
      (node (ref "D2") (pin "A") (pinfunction "A_A") (pintype "passive"))
      (node (ref "Q5") (pin "D") (pinfunction "D_D") (pintype "passive"))
      (node (ref "SPK1") (pin "2") (pinfunction "-_2") (pintype "passive"))
    )
    (net (code "45") (name "Net-(U3-OUT)") (class "Default")
      (node (ref "R16") (pin "1") (pinfunction "1_1") (pintype "passive"))
      (node (ref "U3") (pin "6") (pinfunction "OUT_6") (pintype "output"))
    )
    (net (code "46") (name "Net-(U3-REF)") (class "Default")
      (node (ref "R14") (pin "2") (pinfunction "2_2") (pintype "passive"))
      (node (ref "R15") (pin "1") (pinfunction "1_1") (pintype "passive"))
      (node (ref "U3") (pin "7") (pinfunction "REF_7") (pintype "input"))
    )
    (net (code "47") (name "Net-(U4-SW-Pad5)") (class "Default")
      (node (ref "U4") (pin "5") (pinfunction "SW_5") (pintype "power_in"))
      (node (ref "U4") (pin "6") (pinfunction "SW_6") (pintype "power_in"))
    )
    (net (code "48") (name "Net-(U4-VCC)") (class "Default")
      (node (ref "C16") (pin "2") (pinfunction "2_2") (pintype "passive"))
      (node (ref "U4") (pin "8") (pinfunction "VCC_8") (pintype "power_in"))
    )
    (net (code "49") (name "V+") (class "Default")
      (node (ref "H3") (pin "HOLE") (pinfunction "HOLE_HOLE") (pintype "passive"))
      (node (ref "H6") (pin "HOLE") (pinfunction "HOLE_HOLE") (pintype "passive"))
      (node (ref "Q2") (pin "D") (pinfunction "D_D") (pintype "passive"))
      (node (ref "TVS1") (pin "A") (pinfunction "A_A") (pintype "passive"))
    )
    (net (code "50") (name "V-") (class "Default")
      (node (ref "H2") (pin "HOLE") (pinfunction "HOLE_HOLE") (pintype "passive"))
      (node (ref "H5") (pin "HOLE") (pinfunction "HOLE_HOLE") (pintype "passive"))
      (node (ref "R13") (pin "2") (pinfunction "2_2") (pintype "passive"))
      (node (ref "TVS1") (pin "C") (pinfunction "C_C") (pintype "passive"))
    )
    (net (code "51") (name "VBAT") (class "Default")
      (node (ref "C2") (pin "2") (pinfunction "2_2") (pintype "passive"))
      (node (ref "C3") (pin "2") (pinfunction "2_2") (pintype "passive"))
      (node (ref "J2") (pin "1") (pinfunction "1_1") (pintype "passive"))
      (node (ref "Q1") (pin "D") (pinfunction "D_D") (pintype "passive"))
      (node (ref "R17") (pin "1") (pinfunction "1_1") (pintype "passive"))
      (node (ref "U4") (pin "2") (pinfunction "EN_2") (pintype "input"))
      (node (ref "U4") (pin "3") (pinfunction "VIN_3") (pintype "power_in"))
    )
    (net (code "52") (name "unconnected-(U1-PA1-Pad7)") (class "Default")
      (node (ref "U1") (pin "7") (pinfunction "PA1_7") (pintype "bidirectional"))
    )
    (net (code "53") (name "unconnected-(U1-PA4-Pad10)") (class "Default")
      (node (ref "U1") (pin "10") (pinfunction "PA4_10") (pintype "bidirectional"))
    )
    (net (code "54") (name "unconnected-(U1-PA6-Pad12)") (class "Default")
      (node (ref "U1") (pin "12") (pinfunction "PA6_12") (pintype "bidirectional"))
    )
    (net (code "55") (name "unconnected-(U1-PA9-Pad19)") (class "Default")
      (node (ref "U1") (pin "19") (pinfunction "PA9_19") (pintype "bidirectional"))
    )
    (net (code "56") (name "unconnected-(U1-PB4-Pad27)") (class "Default")
      (node (ref "U1") (pin "27") (pinfunction "PB4_27") (pintype "bidirectional"))
    )
    (net (code "57") (name "unconnected-(U1-PB5-Pad28)") (class "Default")
      (node (ref "U1") (pin "28") (pinfunction "PB5_28") (pintype "bidirectional"))
    )
    (net (code "58") (name "unconnected-(U1-PC14_{slash}_OSC32_IN-Pad2)") (class "Default")
      (node (ref "U1") (pin "2") (pinfunction "PC14_/_OSC32_IN_2") (pintype "bidirectional"))
    )
    (net (code "59") (name "unconnected-(U1-PC15_{slash}_OSC32_OUT-Pad3)") (class "Default")
      (node (ref "U1") (pin "3") (pinfunction "PC15_/_OSC32_OUT_3") (pintype "bidirectional"))
    )
    (net (code "60") (name "unconnected-(U4-BOOT-Pad7)") (class "Default")
      (node (ref "U4") (pin "7") (pinfunction "BOOT_7") (pintype "power_in+no_connect"))
    )
    (net (code "61") (name "unconnected-(U4-PGOOD-Pad1)") (class "Default")
      (node (ref "U4") (pin "1") (pinfunction "PGOOD_1") (pintype "open_collector+no_connect"))
    )
  )
)
